# EXT_DC_OUT.net
KiCad netlist of a schematic drawn in EAGLE
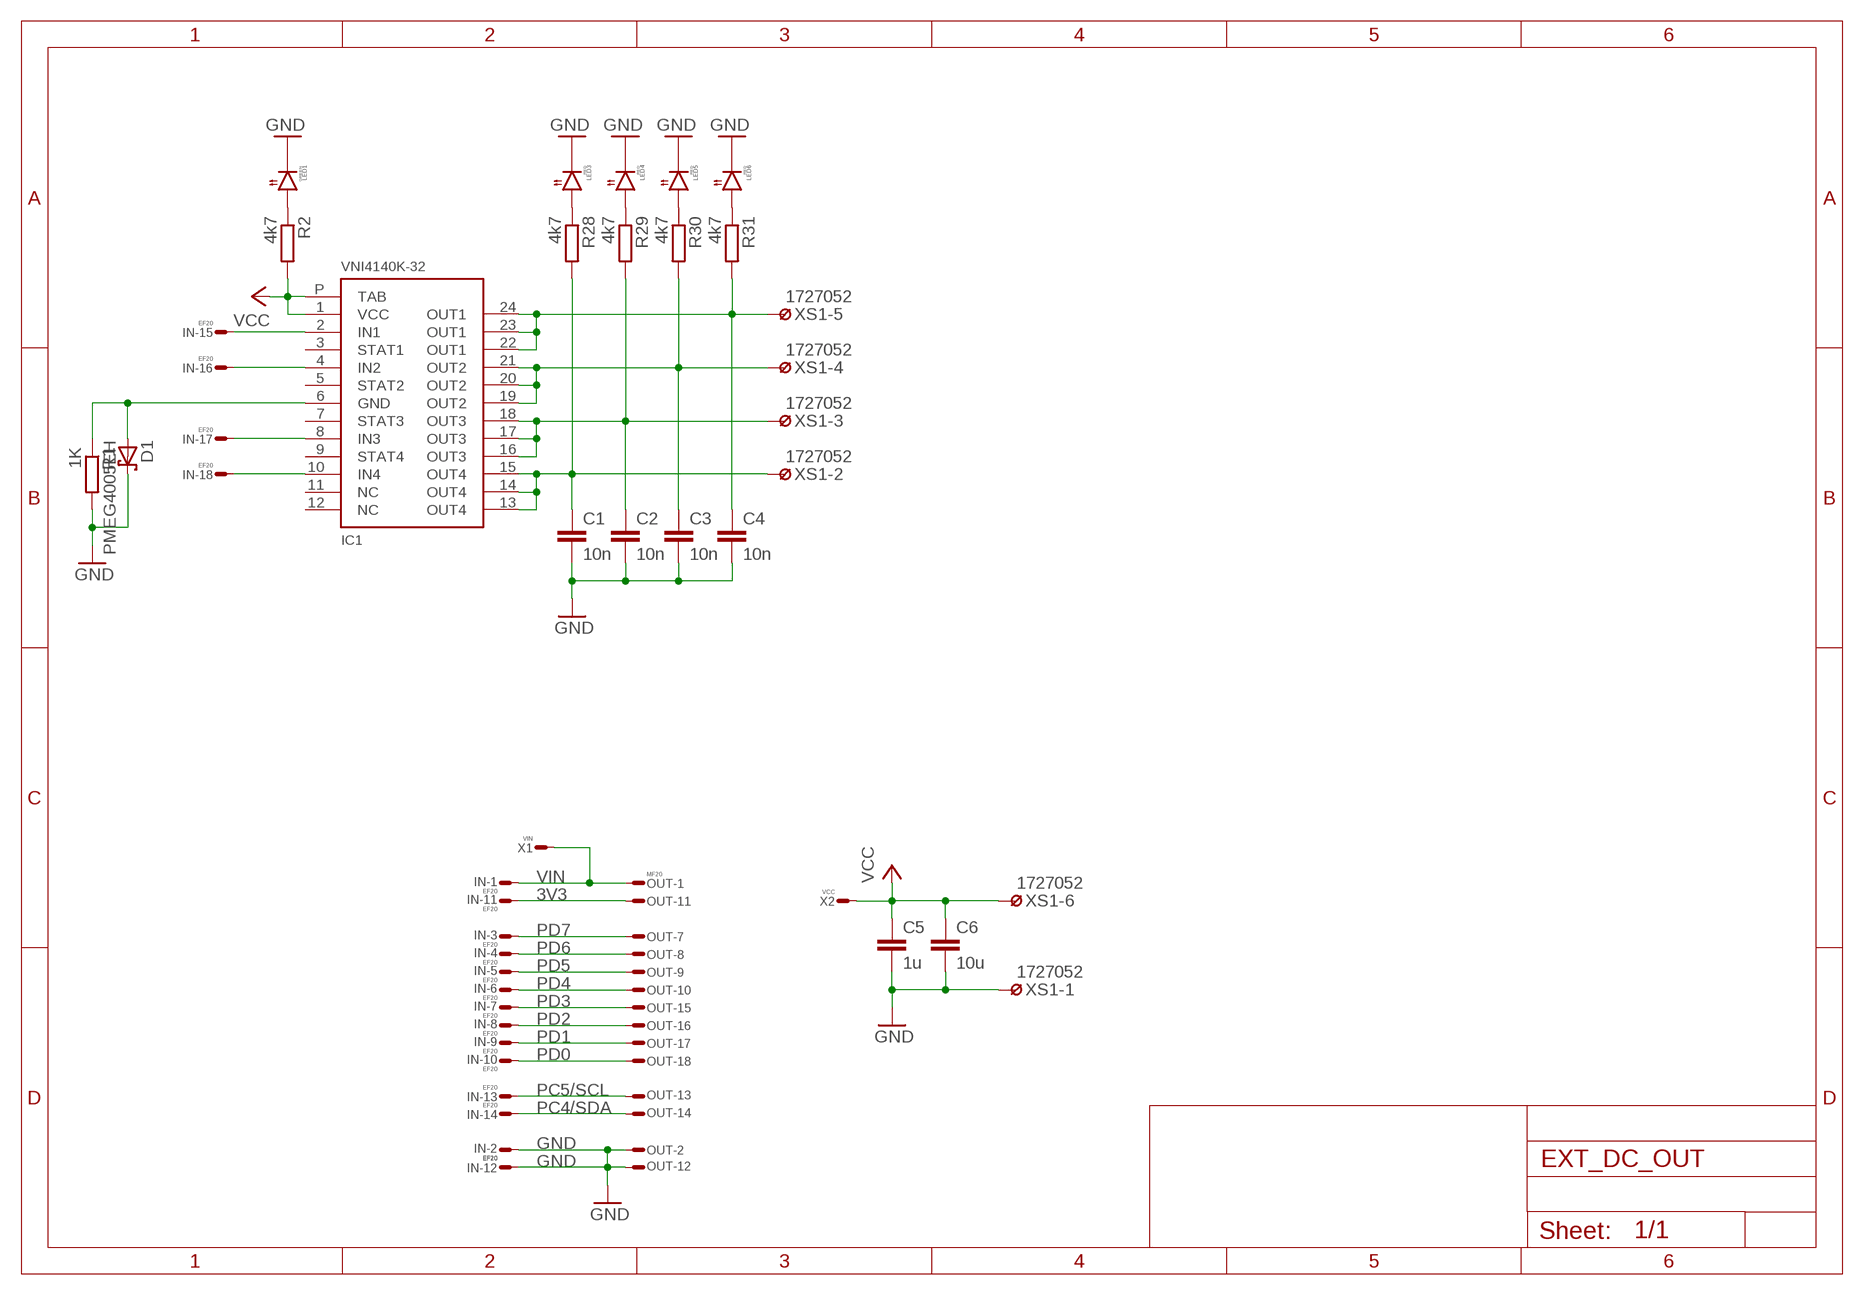
[diagram p0: schematic, sheet 1]

(export (version "E")
  (design (tool "Eeschema 10.0.6"))
  (components
    (comp (ref "C1")
      (value "10n")
      (footprint "eagle-import:1206")
      (libsource (lib "eagle-import") (part "C1206"))
    )
    (comp (ref "C2")
      (value "10n")
      (footprint "eagle-import:1206")
      (libsource (lib "eagle-import") (part "C1206"))
    )
    (comp (ref "C3")
      (value "10n")
      (footprint "eagle-import:1206")
      (libsource (lib "eagle-import") (part "C1206"))
    )
    (comp (ref "C4")
      (value "10n")
      (footprint "eagle-import:1206")
      (libsource (lib "eagle-import") (part "C1206"))
    )
    (comp (ref "C5")
      (value "1u")
      (footprint "eagle-import:1206")
      (libsource (lib "eagle-import") (part "C1206"))
    )
    (comp (ref "C6")
      (value "10u")
      (footprint "eagle-import:C1210")
      (libsource (lib "eagle-import") (part "CC1210"))
    )
    (comp (ref "D1")
      (value "PMEG4005EH")
      (footprint "eagle-import:SOD123")
      (libsource (lib "eagle-import") (part "D-SCHOTKY123"))
    )
    (comp (ref "IC1")
      (value "VNI4140K-32")
      (footprint "eagle-import:PSSO-24")
      (libsource (lib "eagle-import") (part "VNI4140"))
    )
    (comp (ref "IN")
      (value "EF20")
      (footprint "eagle-import:FE10-2WS")
      (libsource (lib "eagle-import") (part "FE20ELS"))
    )
    (comp (ref "LED1")
      (value "GREEN")
      (footprint "eagle-import:1206")
      (libsource (lib "eagle-import") (part "LED1206"))
    )
    (comp (ref "LED3")
      (value "RED")
      (footprint "eagle-import:1206")
      (libsource (lib "eagle-import") (part "LED1206"))
    )
    (comp (ref "LED4")
      (value "RED")
      (footprint "eagle-import:1206")
      (libsource (lib "eagle-import") (part "LED1206"))
    )
    (comp (ref "LED5")
      (value "RED")
      (footprint "eagle-import:1206")
      (libsource (lib "eagle-import") (part "LED1206"))
    )
    (comp (ref "LED6")
      (value "RED")
      (footprint "eagle-import:1206")
      (libsource (lib "eagle-import") (part "LED1206"))
    )
    (comp (ref "OUT")
      (value "MF20")
      (footprint "eagle-import:ML20LS")
      (libsource (lib "eagle-import") (part "ML20?ELS"))
    )
    (comp (ref "R1")
      (value "1K")
      (footprint "eagle-import:1206")
      (libsource (lib "eagle-import") (part "R1206"))
    )
    (comp (ref "R2")
      (value "4k7")
      (footprint "eagle-import:1206")
      (libsource (lib "eagle-import") (part "R1206"))
    )
    (comp (ref "R28")
      (value "4k7")
      (footprint "eagle-import:1206")
      (libsource (lib "eagle-import") (part "R1206"))
    )
    (comp (ref "R29")
      (value "4k7")
      (footprint "eagle-import:1206")
      (libsource (lib "eagle-import") (part "R1206"))
    )
    (comp (ref "R30")
      (value "4k7")
      (footprint "eagle-import:1206")
      (libsource (lib "eagle-import") (part "R1206"))
    )
    (comp (ref "R31")
      (value "4k7")
      (footprint "eagle-import:1206")
      (libsource (lib "eagle-import") (part "R1206"))
    )
    (comp (ref "X1")
      (value "VIN")
      (footprint "eagle-import:T1.6_0.9")
      (libsource (lib "eagle-import") (part "WIREPADT1.6/0.9"))
    )
    (comp (ref "X2")
      (value "VCC")
      (footprint "eagle-import:T1.6_0.9")
      (libsource (lib "eagle-import") (part "WIREPADT1.6/0.9"))
    )
    (comp (ref "XS1")
      (value "1727052")
      (footprint "eagle-import:1727052")
      (libsource (lib "eagle-import") (part "1727052"))
    )
  )
  (nets
    (net (code "1") (name "/3V3") (class "Default")
      (node (ref "IN") (pin "P$11") (pinfunction "S_P$11") (pintype "passive"))
      (node (ref "OUT") (pin "P$11") (pinfunction "S_P$11") (pintype "passive"))
    )
    (net (code "2") (name "/PC4{slash}SDA") (class "Default")
      (node (ref "IN") (pin "P$14") (pinfunction "S_P$14") (pintype "passive"))
      (node (ref "OUT") (pin "P$14") (pinfunction "S_P$14") (pintype "passive"))
    )
    (net (code "3") (name "/PC5{slash}SCL") (class "Default")
      (node (ref "IN") (pin "P$13") (pinfunction "S_P$13") (pintype "passive"))
      (node (ref "OUT") (pin "P$13") (pinfunction "S_P$13") (pintype "passive"))
    )
    (net (code "4") (name "/PD0") (class "Default")
      (node (ref "IN") (pin "P$10") (pinfunction "S_P$10") (pintype "passive"))
      (node (ref "OUT") (pin "P$18") (pinfunction "S_P$18") (pintype "passive"))
    )
    (net (code "5") (name "/PD1") (class "Default")
      (node (ref "IN") (pin "P$9") (pinfunction "S_P$9") (pintype "passive"))
      (node (ref "OUT") (pin "P$17") (pinfunction "S_P$17") (pintype "passive"))
    )
    (net (code "6") (name "/PD2") (class "Default")
      (node (ref "IN") (pin "P$8") (pinfunction "S_P$8") (pintype "passive"))
      (node (ref "OUT") (pin "P$16") (pinfunction "S_P$16") (pintype "passive"))
    )
    (net (code "7") (name "/PD3") (class "Default")
      (node (ref "IN") (pin "P$7") (pinfunction "S_P$7") (pintype "passive"))
      (node (ref "OUT") (pin "P$15") (pinfunction "S_P$15") (pintype "passive"))
    )
    (net (code "8") (name "/PD4") (class "Default")
      (node (ref "IN") (pin "P$6") (pinfunction "S_P$6") (pintype "passive"))
      (node (ref "OUT") (pin "P$10") (pinfunction "S_P$10") (pintype "passive"))
    )
    (net (code "9") (name "/PD5") (class "Default")
      (node (ref "IN") (pin "P$5") (pinfunction "S_P$5") (pintype "passive"))
      (node (ref "OUT") (pin "P$9") (pinfunction "S_P$9") (pintype "passive"))
    )
    (net (code "10") (name "/PD6") (class "Default")
      (node (ref "IN") (pin "P$4") (pinfunction "S_P$4") (pintype "passive"))
      (node (ref "OUT") (pin "P$8") (pinfunction "S_P$8") (pintype "passive"))
    )
    (net (code "11") (name "/PD7") (class "Default")
      (node (ref "IN") (pin "P$3") (pinfunction "S_P$3") (pintype "passive"))
      (node (ref "OUT") (pin "P$7") (pinfunction "S_P$7") (pintype "passive"))
    )
    (net (code "12") (name "/VIN") (class "Default")
      (node (ref "IN") (pin "P$1") (pinfunction "S_P$1") (pintype "passive"))
      (node (ref "OUT") (pin "P$1") (pinfunction "S_P$1") (pintype "passive"))
      (node (ref "X1") (pin "1") (pinfunction "S_1") (pintype "passive"))
    )
    (net (code "13") (name "GND") (class "Default")
      (node (ref "C1") (pin "2") (pinfunction "2_2") (pintype "passive"))
      (node (ref "C2") (pin "2") (pinfunction "2_2") (pintype "passive"))
      (node (ref "C3") (pin "2") (pinfunction "2_2") (pintype "passive"))
      (node (ref "C4") (pin "2") (pinfunction "2_2") (pintype "passive"))
      (node (ref "C5") (pin "2") (pinfunction "2_2") (pintype "passive"))
      (node (ref "C6") (pin "2") (pinfunction "2_2") (pintype "passive"))
      (node (ref "D1") (pin "C") (pinfunction "C_C") (pintype "passive"))
      (node (ref "IN") (pin "P$12") (pinfunction "S_P$12") (pintype "passive"))
      (node (ref "IN") (pin "P$2") (pinfunction "S_P$2") (pintype "passive"))
      (node (ref "LED1") (pin "2") (pinfunction "C_2") (pintype "bidirectional"))
      (node (ref "LED3") (pin "2") (pinfunction "C_2") (pintype "bidirectional"))
      (node (ref "LED4") (pin "2") (pinfunction "C_2") (pintype "bidirectional"))
      (node (ref "LED5") (pin "2") (pinfunction "C_2") (pintype "bidirectional"))
      (node (ref "LED6") (pin "2") (pinfunction "C_2") (pintype "bidirectional"))
      (node (ref "OUT") (pin "P$12") (pinfunction "S_P$12") (pintype "passive"))
      (node (ref "OUT") (pin "P$2") (pinfunction "S_P$2") (pintype "passive"))
      (node (ref "R1") (pin "2") (pinfunction "2_2") (pintype "passive"))
      (node (ref "XS1") (pin "1") (pinfunction "K_1") (pintype "passive"))
    )
    (net (code "14") (name "Net-(IC1-GND)") (class "Default")
      (node (ref "D1") (pin "A") (pinfunction "A_A") (pintype "passive"))
      (node (ref "IC1") (pin "6") (pinfunction "GND_6") (pintype "input"))
      (node (ref "R1") (pin "1") (pinfunction "1_1") (pintype "passive"))
    )
    (net (code "15") (name "Net-(IC1-IN1)") (class "Default")
      (node (ref "IC1") (pin "2") (pinfunction "IN1_2") (pintype "input"))
      (node (ref "IN") (pin "P$15") (pinfunction "S_P$15") (pintype "passive"))
    )
    (net (code "16") (name "Net-(IC1-IN2)") (class "Default")
      (node (ref "IC1") (pin "4") (pinfunction "IN2_4") (pintype "input"))
      (node (ref "IN") (pin "P$16") (pinfunction "S_P$16") (pintype "passive"))
    )
    (net (code "17") (name "Net-(IC1-IN3)") (class "Default")
      (node (ref "IC1") (pin "8") (pinfunction "IN3_8") (pintype "input"))
      (node (ref "IN") (pin "P$17") (pinfunction "S_P$17") (pintype "passive"))
    )
    (net (code "18") (name "Net-(IC1-IN4)") (class "Default")
      (node (ref "IC1") (pin "10") (pinfunction "IN4_10") (pintype "input"))
      (node (ref "IN") (pin "P$18") (pinfunction "S_P$18") (pintype "passive"))
    )
    (net (code "19") (name "Net-(LED1-A)") (class "Default")
      (node (ref "LED1") (pin "1") (pinfunction "A_1") (pintype "bidirectional"))
      (node (ref "R2") (pin "1") (pinfunction "1_1") (pintype "passive"))
    )
    (net (code "20") (name "Net-(LED3-A)") (class "Default")
      (node (ref "LED3") (pin "1") (pinfunction "A_1") (pintype "bidirectional"))
      (node (ref "R28") (pin "1") (pinfunction "1_1") (pintype "passive"))
    )
    (net (code "21") (name "Net-(LED4-A)") (class "Default")
      (node (ref "LED4") (pin "1") (pinfunction "A_1") (pintype "bidirectional"))
      (node (ref "R29") (pin "1") (pinfunction "1_1") (pintype "passive"))
    )
    (net (code "22") (name "Net-(LED5-A)") (class "Default")
      (node (ref "LED5") (pin "1") (pinfunction "A_1") (pintype "bidirectional"))
      (node (ref "R30") (pin "1") (pinfunction "1_1") (pintype "passive"))
    )
    (net (code "23") (name "Net-(LED6-A)") (class "Default")
      (node (ref "LED6") (pin "1") (pinfunction "A_1") (pintype "bidirectional"))
      (node (ref "R31") (pin "1") (pinfunction "1_1") (pintype "passive"))
    )
    (net (code "24") (name "Net-(XS1B-K)") (class "Default")
      (node (ref "C1") (pin "1") (pinfunction "1_1") (pintype "passive"))
      (node (ref "IC1") (pin "13") (pinfunction "OUT4_13") (pintype "tri_state"))
      (node (ref "IC1") (pin "14") (pinfunction "OUT4_14") (pintype "tri_state"))
      (node (ref "IC1") (pin "15") (pinfunction "OUT4_15") (pintype "tri_state"))
      (node (ref "R28") (pin "2") (pinfunction "2_2") (pintype "passive"))
      (node (ref "XS1") (pin "2") (pinfunction "K_2") (pintype "passive"))
    )
    (net (code "25") (name "Net-(XS1C-K)") (class "Default")
      (node (ref "C2") (pin "1") (pinfunction "1_1") (pintype "passive"))
      (node (ref "IC1") (pin "16") (pinfunction "OUT3_16") (pintype "tri_state"))
      (node (ref "IC1") (pin "17") (pinfunction "OUT3_17") (pintype "tri_state"))
      (node (ref "IC1") (pin "18") (pinfunction "OUT3_18") (pintype "tri_state"))
      (node (ref "R29") (pin "2") (pinfunction "2_2") (pintype "passive"))
      (node (ref "XS1") (pin "3") (pinfunction "K_3") (pintype "passive"))
    )
    (net (code "26") (name "Net-(XS1D-K)") (class "Default")
      (node (ref "C3") (pin "1") (pinfunction "1_1") (pintype "passive"))
      (node (ref "IC1") (pin "19") (pinfunction "OUT2_19") (pintype "tri_state"))
      (node (ref "IC1") (pin "20") (pinfunction "OUT2_20") (pintype "tri_state"))
      (node (ref "IC1") (pin "21") (pinfunction "OUT2_21") (pintype "tri_state"))
      (node (ref "R30") (pin "2") (pinfunction "2_2") (pintype "passive"))
      (node (ref "XS1") (pin "4") (pinfunction "K_4") (pintype "passive"))
    )
    (net (code "27") (name "Net-(XS1E-K)") (class "Default")
      (node (ref "C4") (pin "1") (pinfunction "1_1") (pintype "passive"))
      (node (ref "IC1") (pin "22") (pinfunction "OUT1_22") (pintype "tri_state"))
      (node (ref "IC1") (pin "23") (pinfunction "OUT1_23") (pintype "tri_state"))
      (node (ref "IC1") (pin "24") (pinfunction "OUT1_24") (pintype "tri_state"))
      (node (ref "R31") (pin "2") (pinfunction "2_2") (pintype "passive"))
      (node (ref "XS1") (pin "5") (pinfunction "K_5") (pintype "passive"))
    )
    (net (code "28") (name "VCC") (class "Default")
      (node (ref "C5") (pin "1") (pinfunction "1_1") (pintype "passive"))
      (node (ref "C6") (pin "1") (pinfunction "1_1") (pintype "passive"))
      (node (ref "IC1") (pin "1") (pinfunction "VCC_1") (pintype "input"))
      (node (ref "IC1") (pin "P") (pinfunction "TAB_P") (pintype "input"))
      (node (ref "R2") (pin "2") (pinfunction "2_2") (pintype "passive"))
      (node (ref "X2") (pin "1") (pinfunction "S_1") (pintype "passive"))
      (node (ref "XS1") (pin "6") (pinfunction "K_6") (pintype "passive"))
    )
    (net (code "29") (name "unconnected-(IC1-NC-Pad11)") (class "Default")
      (node (ref "IC1") (pin "11") (pinfunction "NC_11") (pintype "no_connect"))
    )
    (net (code "30") (name "unconnected-(IC1-NC-Pad12)") (class "Default")
      (node (ref "IC1") (pin "12") (pinfunction "NC_12") (pintype "no_connect"))
    )
    (net (code "31") (name "unconnected-(IC1-STAT1-Pad3)") (class "Default")
      (node (ref "IC1") (pin "3") (pinfunction "STAT1_3") (pintype "output"))
    )
    (net (code "32") (name "unconnected-(IC1-STAT2-Pad5)") (class "Default")
      (node (ref "IC1") (pin "5") (pinfunction "STAT2_5") (pintype "output"))
    )
    (net (code "33") (name "unconnected-(IC1-STAT3-Pad7)") (class "Default")
      (node (ref "IC1") (pin "7") (pinfunction "STAT3_7") (pintype "output"))
    )
    (net (code "34") (name "unconnected-(IC1-STAT4-Pad9)") (class "Default")
      (node (ref "IC1") (pin "9") (pinfunction "STAT4_9") (pintype "output"))
    )
  )
)
